# lqfp_adapters.net
KiCad netlist of a schematic drawn in EAGLE
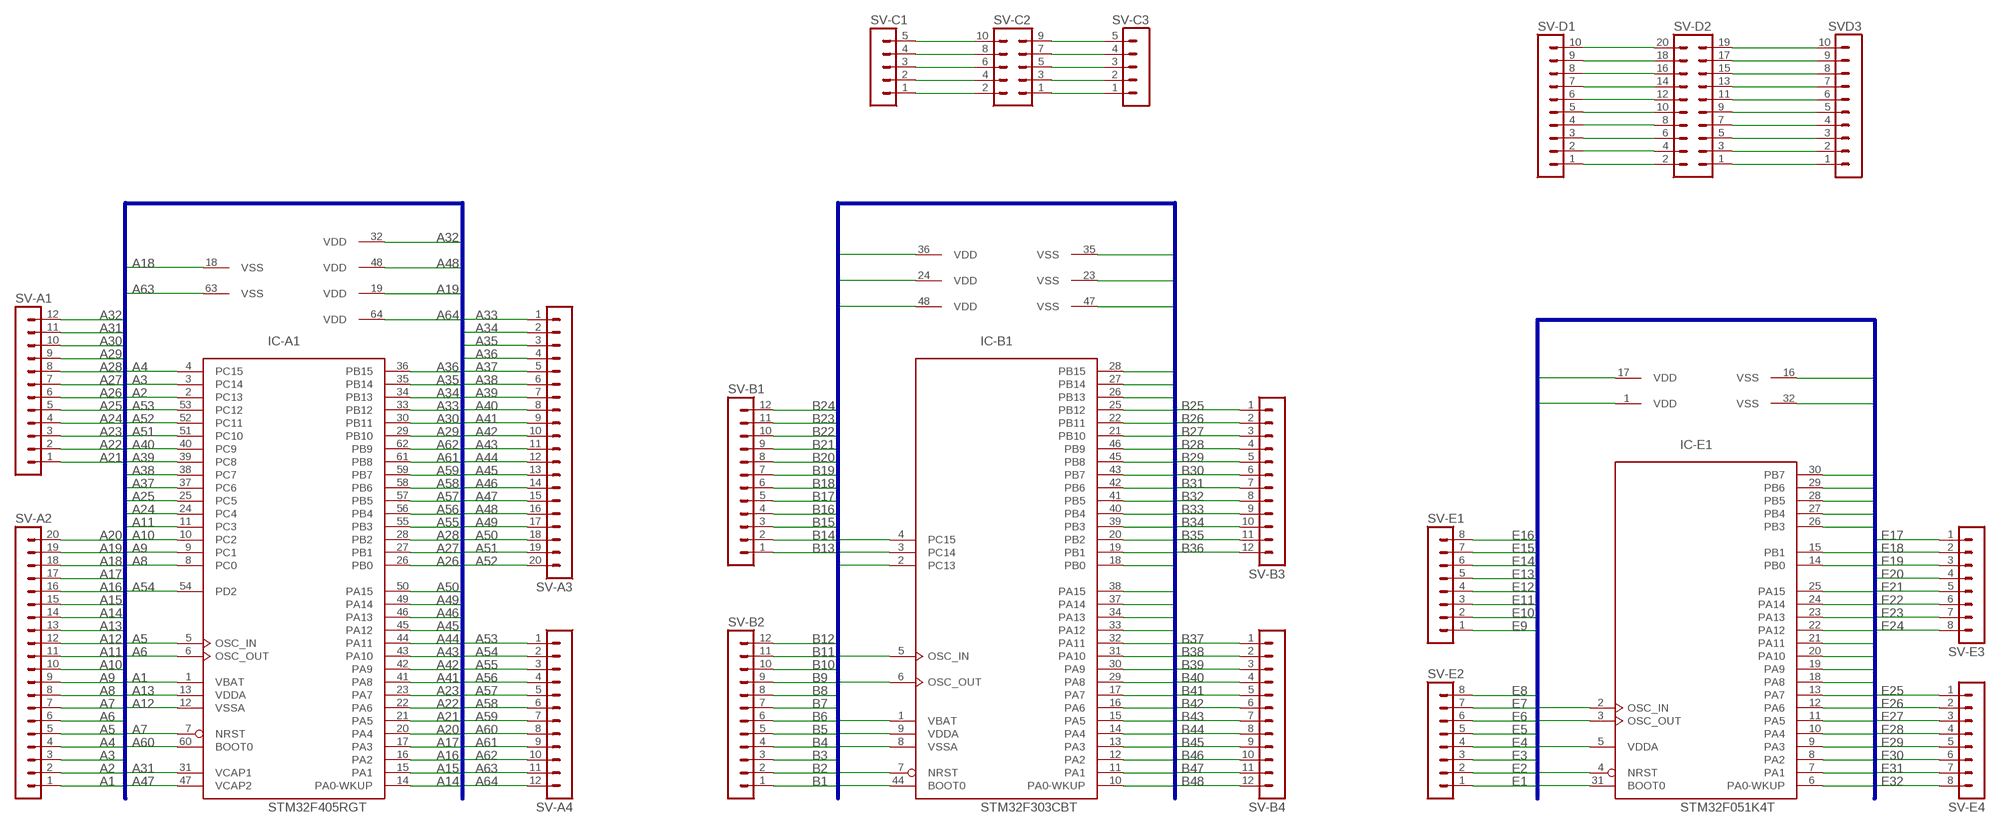
[diagram p0: schematic, sheet 1]

(export (version "E")
  (design (tool "Eeschema 10.0.6"))
  (components
    (comp (ref "IC-A1")
      (value "STM32F405RGT")
      (footprint "eagle-import:LQFP64")
      (libsource (lib "eagle-import") (part "STM32F405RTG"))
    )
    (comp (ref "IC-B1")
      (value "STM32F303CBT")
      (footprint "eagle-import:LQFP48")
      (libsource (lib "eagle-import") (part "STM32F303CTB"))
    )
    (comp (ref "IC-E1")
      (value "STM32F051K4T")
      (footprint "eagle-import:LQFP32")
      (libsource (lib "eagle-import") (part "STM32F051KT4"))
    )
    (comp (ref "SV-A1")
      (value "MA12-1NO-PL")
      (footprint "eagle-import:MA12-1-NO-PL")
      (libsource (lib "eagle-import") (part "MA12-1NO-PL"))
    )
    (comp (ref "SV-A2")
      (value "MA20-1NO-PL")
      (footprint "eagle-import:MA20-1-NO-PL")
      (libsource (lib "eagle-import") (part "MA20-1NO-PL"))
    )
    (comp (ref "SV-A3")
      (value "MA20-1NO-PL")
      (footprint "eagle-import:MA20-1-NO-PL")
      (libsource (lib "eagle-import") (part "MA20-1NO-PL"))
    )
    (comp (ref "SV-A4")
      (value "MA12-1NO-PL")
      (footprint "eagle-import:MA12-1-NO-PL")
      (libsource (lib "eagle-import") (part "MA12-1NO-PL"))
    )
    (comp (ref "SV-B1")
      (value "MA12-1NO-PL")
      (footprint "eagle-import:MA12-1-NO-PL")
      (libsource (lib "eagle-import") (part "MA12-1NO-PL"))
    )
    (comp (ref "SV-B2")
      (value "MA12-1NO-PL")
      (footprint "eagle-import:MA12-1-NO-PL")
      (libsource (lib "eagle-import") (part "MA12-1NO-PL"))
    )
    (comp (ref "SV-B3")
      (value "MA12-1NO-PL")
      (footprint "eagle-import:MA12-1-NO-PL")
      (libsource (lib "eagle-import") (part "MA12-1NO-PL"))
    )
    (comp (ref "SV-B4")
      (value "MA12-1NO-PL")
      (footprint "eagle-import:MA12-1-NO-PL")
      (libsource (lib "eagle-import") (part "MA12-1NO-PL"))
    )
    (comp (ref "SV-C1")
      (value "MA05-1NO-PL")
      (footprint "eagle-import:MA05-1-NO-PL")
      (libsource (lib "eagle-import") (part "MA05-1NO-PL"))
    )
    (comp (ref "SV-C2")
      (value "MA05-2")
      (footprint "eagle-import:MA05-2")
      (libsource (lib "eagle-import") (part "MA05-2"))
    )
    (comp (ref "SV-C3")
      (value "MA05-1NO-PL")
      (footprint "eagle-import:MA05-1-NO-PL")
      (libsource (lib "eagle-import") (part "MA05-1NO-PL"))
    )
    (comp (ref "SV-D1")
      (value "MA10-1NO-PL")
      (footprint "eagle-import:MA10-1-NO-PL")
      (libsource (lib "eagle-import") (part "MA10-1NO-PL"))
    )
    (comp (ref "SV-D2")
      (value "MA10-2")
      (footprint "eagle-import:MA10-2")
      (libsource (lib "eagle-import") (part "MA10-2"))
    )
    (comp (ref "SV-E1")
      (value "MA08-1NO-PL")
      (footprint "eagle-import:MA08-1-NO-PL")
      (libsource (lib "eagle-import") (part "MA08-1NO-PL"))
    )
    (comp (ref "SV-E2")
      (value "MA08-1NO-PL")
      (footprint "eagle-import:MA08-1-NO-PL")
      (libsource (lib "eagle-import") (part "MA08-1NO-PL"))
    )
    (comp (ref "SV-E3")
      (value "MA08-1NO-PL")
      (footprint "eagle-import:MA08-1-NO-PL")
      (libsource (lib "eagle-import") (part "MA08-1NO-PL"))
    )
    (comp (ref "SV-E4")
      (value "MA08-1NO-PL")
      (footprint "eagle-import:MA08-1-NO-PL")
      (libsource (lib "eagle-import") (part "MA08-1NO-PL"))
    )
    (comp (ref "SVD3")
      (value "MA10-1NO-PL")
      (footprint "eagle-import:MA10-1-NO-PL")
      (libsource (lib "eagle-import") (part "MA10-1NO-PL"))
    )
  )
  (nets
    (net (code "1") (name "/A1") (class "Default")
      (node (ref "IC-A1") (pin "1") (pinfunction "VBAT_1") (pintype "power_in"))
      (node (ref "SV-A2") (pin "1") (pinfunction "1_1") (pintype "passive"))
    )
    (net (code "2") (name "/A2") (class "Default")
      (node (ref "IC-A1") (pin "2") (pinfunction "PC13_2") (pintype "bidirectional"))
      (node (ref "SV-A2") (pin "2") (pinfunction "2_2") (pintype "passive"))
    )
    (net (code "3") (name "/A3") (class "Default")
      (node (ref "IC-A1") (pin "3") (pinfunction "PC14_3") (pintype "bidirectional"))
      (node (ref "SV-A2") (pin "3") (pinfunction "3_3") (pintype "passive"))
    )
    (net (code "4") (name "/A4") (class "Default")
      (node (ref "IC-A1") (pin "4") (pinfunction "PC15_4") (pintype "bidirectional"))
      (node (ref "SV-A2") (pin "4") (pinfunction "4_4") (pintype "passive"))
    )
    (net (code "5") (name "/A5") (class "Default")
      (node (ref "IC-A1") (pin "5") (pinfunction "OSC_IN_5") (pintype "bidirectional"))
      (node (ref "SV-A2") (pin "5") (pinfunction "5_5") (pintype "passive"))
    )
    (net (code "6") (name "/A6") (class "Default")
      (node (ref "IC-A1") (pin "6") (pinfunction "OSC_OUT_6") (pintype "bidirectional"))
      (node (ref "SV-A2") (pin "6") (pinfunction "6_6") (pintype "passive"))
    )
    (net (code "7") (name "/A7") (class "Default")
      (node (ref "IC-A1") (pin "7") (pinfunction "NRST_7") (pintype "bidirectional"))
      (node (ref "SV-A2") (pin "7") (pinfunction "7_7") (pintype "passive"))
    )
    (net (code "8") (name "/A8") (class "Default")
      (node (ref "IC-A1") (pin "8") (pinfunction "PC0_8") (pintype "bidirectional"))
      (node (ref "SV-A2") (pin "8") (pinfunction "8_8") (pintype "passive"))
    )
    (net (code "9") (name "/A9") (class "Default")
      (node (ref "IC-A1") (pin "9") (pinfunction "PC1_9") (pintype "bidirectional"))
      (node (ref "SV-A2") (pin "9") (pinfunction "9_9") (pintype "passive"))
    )
    (net (code "10") (name "/A10") (class "Default")
      (node (ref "IC-A1") (pin "10") (pinfunction "PC2_10") (pintype "bidirectional"))
      (node (ref "SV-A2") (pin "10") (pinfunction "10_10") (pintype "passive"))
    )
    (net (code "11") (name "/A11") (class "Default")
      (node (ref "IC-A1") (pin "11") (pinfunction "PC3_11") (pintype "bidirectional"))
      (node (ref "SV-A2") (pin "11") (pinfunction "11_11") (pintype "passive"))
    )
    (net (code "12") (name "/A12") (class "Default")
      (node (ref "IC-A1") (pin "12") (pinfunction "VSSA_12") (pintype "power_in"))
      (node (ref "SV-A2") (pin "12") (pinfunction "12_12") (pintype "passive"))
    )
    (net (code "13") (name "/A13") (class "Default")
      (node (ref "IC-A1") (pin "13") (pinfunction "VDDA_13") (pintype "power_in"))
      (node (ref "SV-A2") (pin "13") (pinfunction "13_13") (pintype "passive"))
    )
    (net (code "14") (name "/A14") (class "Default")
      (node (ref "IC-A1") (pin "14") (pinfunction "PA0-WKUP_14") (pintype "bidirectional"))
      (node (ref "SV-A2") (pin "14") (pinfunction "14_14") (pintype "passive"))
    )
    (net (code "15") (name "/A15") (class "Default")
      (node (ref "IC-A1") (pin "15") (pinfunction "PA1_15") (pintype "bidirectional"))
      (node (ref "SV-A2") (pin "15") (pinfunction "15_15") (pintype "passive"))
    )
    (net (code "16") (name "/A16") (class "Default")
      (node (ref "IC-A1") (pin "16") (pinfunction "PA2_16") (pintype "bidirectional"))
      (node (ref "SV-A2") (pin "16") (pinfunction "16_16") (pintype "passive"))
    )
    (net (code "17") (name "/A17") (class "Default")
      (node (ref "IC-A1") (pin "17") (pinfunction "PA3_17") (pintype "bidirectional"))
      (node (ref "SV-A2") (pin "17") (pinfunction "17_17") (pintype "passive"))
    )
    (net (code "18") (name "/A18") (class "Default")
      (node (ref "IC-A1") (pin "18") (pinfunction "VSS_18") (pintype "power_in"))
      (node (ref "SV-A2") (pin "18") (pinfunction "18_18") (pintype "passive"))
    )
    (net (code "19") (name "/A19") (class "Default")
      (node (ref "IC-A1") (pin "19") (pinfunction "VDD_19") (pintype "power_in"))
      (node (ref "SV-A2") (pin "19") (pinfunction "19_19") (pintype "passive"))
    )
    (net (code "20") (name "/A20") (class "Default")
      (node (ref "IC-A1") (pin "20") (pinfunction "PA4_20") (pintype "bidirectional"))
      (node (ref "SV-A2") (pin "20") (pinfunction "20_20") (pintype "passive"))
    )
    (net (code "21") (name "/A21") (class "Default")
      (node (ref "IC-A1") (pin "21") (pinfunction "PA5_21") (pintype "bidirectional"))
      (node (ref "SV-A1") (pin "1") (pinfunction "1_1") (pintype "passive"))
    )
    (net (code "22") (name "/A22") (class "Default")
      (node (ref "IC-A1") (pin "22") (pinfunction "PA6_22") (pintype "bidirectional"))
      (node (ref "SV-A1") (pin "2") (pinfunction "2_2") (pintype "passive"))
    )
    (net (code "23") (name "/A23") (class "Default")
      (node (ref "IC-A1") (pin "23") (pinfunction "PA7_23") (pintype "bidirectional"))
      (node (ref "SV-A1") (pin "3") (pinfunction "3_3") (pintype "passive"))
    )
    (net (code "24") (name "/A24") (class "Default")
      (node (ref "IC-A1") (pin "24") (pinfunction "PC4_24") (pintype "bidirectional"))
      (node (ref "SV-A1") (pin "4") (pinfunction "4_4") (pintype "passive"))
    )
    (net (code "25") (name "/A25") (class "Default")
      (node (ref "IC-A1") (pin "25") (pinfunction "PC5_25") (pintype "bidirectional"))
      (node (ref "SV-A1") (pin "5") (pinfunction "5_5") (pintype "passive"))
    )
    (net (code "26") (name "/A26") (class "Default")
      (node (ref "IC-A1") (pin "26") (pinfunction "PB0_26") (pintype "bidirectional"))
      (node (ref "SV-A1") (pin "6") (pinfunction "6_6") (pintype "passive"))
    )
    (net (code "27") (name "/A27") (class "Default")
      (node (ref "IC-A1") (pin "27") (pinfunction "PB1_27") (pintype "bidirectional"))
      (node (ref "SV-A1") (pin "7") (pinfunction "7_7") (pintype "passive"))
    )
    (net (code "28") (name "/A28") (class "Default")
      (node (ref "IC-A1") (pin "28") (pinfunction "PB2_28") (pintype "bidirectional"))
      (node (ref "SV-A1") (pin "8") (pinfunction "8_8") (pintype "passive"))
    )
    (net (code "29") (name "/A29") (class "Default")
      (node (ref "IC-A1") (pin "29") (pinfunction "PB10_29") (pintype "bidirectional"))
      (node (ref "SV-A1") (pin "9") (pinfunction "9_9") (pintype "passive"))
    )
    (net (code "30") (name "/A30") (class "Default")
      (node (ref "IC-A1") (pin "30") (pinfunction "PB11_30") (pintype "bidirectional"))
      (node (ref "SV-A1") (pin "10") (pinfunction "10_10") (pintype "passive"))
    )
    (net (code "31") (name "/A31") (class "Default")
      (node (ref "IC-A1") (pin "31") (pinfunction "VCAP1_31") (pintype "power_in"))
      (node (ref "SV-A1") (pin "11") (pinfunction "11_11") (pintype "passive"))
    )
    (net (code "32") (name "/A32") (class "Default")
      (node (ref "IC-A1") (pin "32") (pinfunction "VDD_32") (pintype "power_in"))
      (node (ref "SV-A1") (pin "12") (pinfunction "12_12") (pintype "passive"))
    )
    (net (code "33") (name "/A33") (class "Default")
      (node (ref "IC-A1") (pin "33") (pinfunction "PB12_33") (pintype "bidirectional"))
      (node (ref "SV-A3") (pin "1") (pinfunction "1_1") (pintype "passive"))
    )
    (net (code "34") (name "/A34") (class "Default")
      (node (ref "IC-A1") (pin "34") (pinfunction "PB13_34") (pintype "bidirectional"))
      (node (ref "SV-A3") (pin "2") (pinfunction "2_2") (pintype "passive"))
    )
    (net (code "35") (name "/A35") (class "Default")
      (node (ref "IC-A1") (pin "35") (pinfunction "PB14_35") (pintype "bidirectional"))
      (node (ref "SV-A3") (pin "3") (pinfunction "3_3") (pintype "passive"))
    )
    (net (code "36") (name "/A36") (class "Default")
      (node (ref "IC-A1") (pin "36") (pinfunction "PB15_36") (pintype "bidirectional"))
      (node (ref "SV-A3") (pin "4") (pinfunction "4_4") (pintype "passive"))
    )
    (net (code "37") (name "/A37") (class "Default")
      (node (ref "IC-A1") (pin "37") (pinfunction "PC6_37") (pintype "bidirectional"))
      (node (ref "SV-A3") (pin "5") (pinfunction "5_5") (pintype "passive"))
    )
    (net (code "38") (name "/A38") (class "Default")
      (node (ref "IC-A1") (pin "38") (pinfunction "PC7_38") (pintype "bidirectional"))
      (node (ref "SV-A3") (pin "6") (pinfunction "6_6") (pintype "passive"))
    )
    (net (code "39") (name "/A39") (class "Default")
      (node (ref "IC-A1") (pin "39") (pinfunction "PC8_39") (pintype "bidirectional"))
      (node (ref "SV-A3") (pin "7") (pinfunction "7_7") (pintype "passive"))
    )
    (net (code "40") (name "/A40") (class "Default")
      (node (ref "IC-A1") (pin "40") (pinfunction "PC9_40") (pintype "bidirectional"))
      (node (ref "SV-A3") (pin "8") (pinfunction "8_8") (pintype "passive"))
    )
    (net (code "41") (name "/A41") (class "Default")
      (node (ref "IC-A1") (pin "41") (pinfunction "PA8_41") (pintype "bidirectional"))
      (node (ref "SV-A3") (pin "9") (pinfunction "9_9") (pintype "passive"))
    )
    (net (code "42") (name "/A42") (class "Default")
      (node (ref "IC-A1") (pin "42") (pinfunction "PA9_42") (pintype "bidirectional"))
      (node (ref "SV-A3") (pin "10") (pinfunction "10_10") (pintype "passive"))
    )
    (net (code "43") (name "/A43") (class "Default")
      (node (ref "IC-A1") (pin "43") (pinfunction "PA10_43") (pintype "bidirectional"))
      (node (ref "SV-A3") (pin "11") (pinfunction "11_11") (pintype "passive"))
    )
    (net (code "44") (name "/A44") (class "Default")
      (node (ref "IC-A1") (pin "44") (pinfunction "PA11_44") (pintype "bidirectional"))
      (node (ref "SV-A3") (pin "12") (pinfunction "12_12") (pintype "passive"))
    )
    (net (code "45") (name "/A45") (class "Default")
      (node (ref "IC-A1") (pin "45") (pinfunction "PA12_45") (pintype "bidirectional"))
      (node (ref "SV-A3") (pin "13") (pinfunction "13_13") (pintype "passive"))
    )
    (net (code "46") (name "/A46") (class "Default")
      (node (ref "IC-A1") (pin "46") (pinfunction "PA13_46") (pintype "bidirectional"))
      (node (ref "SV-A3") (pin "14") (pinfunction "14_14") (pintype "passive"))
    )
    (net (code "47") (name "/A47") (class "Default")
      (node (ref "IC-A1") (pin "47") (pinfunction "VCAP2_47") (pintype "power_in"))
      (node (ref "SV-A3") (pin "15") (pinfunction "15_15") (pintype "passive"))
    )
    (net (code "48") (name "/A48") (class "Default")
      (node (ref "IC-A1") (pin "48") (pinfunction "VDD_48") (pintype "power_in"))
      (node (ref "SV-A3") (pin "16") (pinfunction "16_16") (pintype "passive"))
    )
    (net (code "49") (name "/A49") (class "Default")
      (node (ref "IC-A1") (pin "49") (pinfunction "PA14_49") (pintype "bidirectional"))
      (node (ref "SV-A3") (pin "17") (pinfunction "17_17") (pintype "passive"))
    )
    (net (code "50") (name "/A50") (class "Default")
      (node (ref "IC-A1") (pin "50") (pinfunction "PA15_50") (pintype "bidirectional"))
      (node (ref "SV-A3") (pin "18") (pinfunction "18_18") (pintype "passive"))
    )
    (net (code "51") (name "/A51") (class "Default")
      (node (ref "IC-A1") (pin "51") (pinfunction "PC10_51") (pintype "bidirectional"))
      (node (ref "SV-A3") (pin "19") (pinfunction "19_19") (pintype "passive"))
    )
    (net (code "52") (name "/A52") (class "Default")
      (node (ref "IC-A1") (pin "52") (pinfunction "PC11_52") (pintype "bidirectional"))
      (node (ref "SV-A3") (pin "20") (pinfunction "20_20") (pintype "passive"))
    )
    (net (code "53") (name "/A53") (class "Default")
      (node (ref "IC-A1") (pin "53") (pinfunction "PC12_53") (pintype "bidirectional"))
      (node (ref "SV-A4") (pin "1") (pinfunction "1_1") (pintype "passive"))
    )
    (net (code "54") (name "/A54") (class "Default")
      (node (ref "IC-A1") (pin "54") (pinfunction "PD2_54") (pintype "bidirectional"))
      (node (ref "SV-A4") (pin "2") (pinfunction "2_2") (pintype "passive"))
    )
    (net (code "55") (name "/A55") (class "Default")
      (node (ref "IC-A1") (pin "55") (pinfunction "PB3_55") (pintype "bidirectional"))
      (node (ref "SV-A4") (pin "3") (pinfunction "3_3") (pintype "passive"))
    )
    (net (code "56") (name "/A56") (class "Default")
      (node (ref "IC-A1") (pin "56") (pinfunction "PB4_56") (pintype "bidirectional"))
      (node (ref "SV-A4") (pin "4") (pinfunction "4_4") (pintype "passive"))
    )
    (net (code "57") (name "/A57") (class "Default")
      (node (ref "IC-A1") (pin "57") (pinfunction "PB5_57") (pintype "bidirectional"))
      (node (ref "SV-A4") (pin "5") (pinfunction "5_5") (pintype "passive"))
    )
    (net (code "58") (name "/A58") (class "Default")
      (node (ref "IC-A1") (pin "58") (pinfunction "PB6_58") (pintype "bidirectional"))
      (node (ref "SV-A4") (pin "6") (pinfunction "6_6") (pintype "passive"))
    )
    (net (code "59") (name "/A59") (class "Default")
      (node (ref "IC-A1") (pin "59") (pinfunction "PB7_59") (pintype "bidirectional"))
      (node (ref "SV-A4") (pin "7") (pinfunction "7_7") (pintype "passive"))
    )
    (net (code "60") (name "/A60") (class "Default")
      (node (ref "IC-A1") (pin "60") (pinfunction "BOOT0_60") (pintype "input"))
      (node (ref "SV-A4") (pin "8") (pinfunction "8_8") (pintype "passive"))
    )
    (net (code "61") (name "/A61") (class "Default")
      (node (ref "IC-A1") (pin "61") (pinfunction "PB8_61") (pintype "bidirectional"))
      (node (ref "SV-A4") (pin "9") (pinfunction "9_9") (pintype "passive"))
    )
    (net (code "62") (name "/A62") (class "Default")
      (node (ref "IC-A1") (pin "62") (pinfunction "PB9_62") (pintype "bidirectional"))
      (node (ref "SV-A4") (pin "10") (pinfunction "10_10") (pintype "passive"))
    )
    (net (code "63") (name "/A63") (class "Default")
      (node (ref "IC-A1") (pin "63") (pinfunction "VSS_63") (pintype "power_in"))
      (node (ref "SV-A4") (pin "11") (pinfunction "11_11") (pintype "passive"))
    )
    (net (code "64") (name "/A64") (class "Default")
      (node (ref "IC-A1") (pin "64") (pinfunction "VDD_64") (pintype "power_in"))
      (node (ref "SV-A4") (pin "12") (pinfunction "12_12") (pintype "passive"))
    )
    (net (code "65") (name "/B1") (class "Default")
      (node (ref "IC-B1") (pin "1") (pinfunction "VBAT_1") (pintype "power_in"))
      (node (ref "SV-B2") (pin "1") (pinfunction "1_1") (pintype "passive"))
    )
    (net (code "66") (name "/B2") (class "Default")
      (node (ref "IC-B1") (pin "2") (pinfunction "PC13_2") (pintype "bidirectional"))
      (node (ref "SV-B2") (pin "2") (pinfunction "2_2") (pintype "passive"))
    )
    (net (code "67") (name "/B3") (class "Default")
      (node (ref "IC-B1") (pin "3") (pinfunction "PC14_3") (pintype "bidirectional"))
      (node (ref "SV-B2") (pin "3") (pinfunction "3_3") (pintype "passive"))
    )
    (net (code "68") (name "/B4") (class "Default")
      (node (ref "IC-B1") (pin "4") (pinfunction "PC15_4") (pintype "bidirectional"))
      (node (ref "SV-B2") (pin "4") (pinfunction "4_4") (pintype "passive"))
    )
    (net (code "69") (name "/B5") (class "Default")
      (node (ref "IC-B1") (pin "5") (pinfunction "OSC_IN_5") (pintype "bidirectional"))
      (node (ref "SV-B2") (pin "5") (pinfunction "5_5") (pintype "passive"))
    )
    (net (code "70") (name "/B6") (class "Default")
      (node (ref "IC-B1") (pin "6") (pinfunction "OSC_OUT_6") (pintype "bidirectional"))
      (node (ref "SV-B2") (pin "6") (pinfunction "6_6") (pintype "passive"))
    )
    (net (code "71") (name "/B7") (class "Default")
      (node (ref "IC-B1") (pin "7") (pinfunction "NRST_7") (pintype "bidirectional"))
      (node (ref "SV-B2") (pin "7") (pinfunction "7_7") (pintype "passive"))
    )
    (net (code "72") (name "/B8") (class "Default")
      (node (ref "IC-B1") (pin "8") (pinfunction "VSSA_8") (pintype "power_in"))
      (node (ref "SV-B2") (pin "8") (pinfunction "8_8") (pintype "passive"))
    )
    (net (code "73") (name "/B9") (class "Default")
      (node (ref "IC-B1") (pin "9") (pinfunction "VDDA_9") (pintype "power_in"))
      (node (ref "SV-B2") (pin "9") (pinfunction "9_9") (pintype "passive"))
    )
    (net (code "74") (name "/B10") (class "Default")
      (node (ref "IC-B1") (pin "10") (pinfunction "PA0-WKUP_10") (pintype "bidirectional"))
      (node (ref "SV-B2") (pin "10") (pinfunction "10_10") (pintype "passive"))
    )
    (net (code "75") (name "/B11") (class "Default")
      (node (ref "IC-B1") (pin "11") (pinfunction "PA1_11") (pintype "bidirectional"))
      (node (ref "SV-B2") (pin "11") (pinfunction "11_11") (pintype "passive"))
    )
    (net (code "76") (name "/B12") (class "Default")
      (node (ref "IC-B1") (pin "12") (pinfunction "PA2_12") (pintype "bidirectional"))
      (node (ref "SV-B2") (pin "12") (pinfunction "12_12") (pintype "passive"))
    )
    (net (code "77") (name "/B13") (class "Default")
      (node (ref "IC-B1") (pin "13") (pinfunction "PA3_13") (pintype "bidirectional"))
      (node (ref "SV-B1") (pin "1") (pinfunction "1_1") (pintype "passive"))
    )
    (net (code "78") (name "/B14") (class "Default")
      (node (ref "IC-B1") (pin "14") (pinfunction "PA4_14") (pintype "bidirectional"))
      (node (ref "SV-B1") (pin "2") (pinfunction "2_2") (pintype "passive"))
    )
    (net (code "79") (name "/B15") (class "Default")
      (node (ref "IC-B1") (pin "15") (pinfunction "PA5_15") (pintype "bidirectional"))
      (node (ref "SV-B1") (pin "3") (pinfunction "3_3") (pintype "passive"))
    )
    (net (code "80") (name "/B16") (class "Default")
      (node (ref "IC-B1") (pin "16") (pinfunction "PA6_16") (pintype "bidirectional"))
      (node (ref "SV-B1") (pin "4") (pinfunction "4_4") (pintype "passive"))
    )
    (net (code "81") (name "/B17") (class "Default")
      (node (ref "IC-B1") (pin "17") (pinfunction "PA7_17") (pintype "bidirectional"))
      (node (ref "SV-B1") (pin "5") (pinfunction "5_5") (pintype "passive"))
    )
    (net (code "82") (name "/B18") (class "Default")
      (node (ref "IC-B1") (pin "18") (pinfunction "PB0_18") (pintype "bidirectional"))
      (node (ref "SV-B1") (pin "6") (pinfunction "6_6") (pintype "passive"))
    )
    (net (code "83") (name "/B19") (class "Default")
      (node (ref "IC-B1") (pin "19") (pinfunction "PB1_19") (pintype "bidirectional"))
      (node (ref "SV-B1") (pin "7") (pinfunction "7_7") (pintype "passive"))
    )
    (net (code "84") (name "/B20") (class "Default")
      (node (ref "IC-B1") (pin "20") (pinfunction "PB2_20") (pintype "bidirectional"))
      (node (ref "SV-B1") (pin "8") (pinfunction "8_8") (pintype "passive"))
    )
    (net (code "85") (name "/B21") (class "Default")
      (node (ref "IC-B1") (pin "21") (pinfunction "PB10_21") (pintype "bidirectional"))
      (node (ref "SV-B1") (pin "9") (pinfunction "9_9") (pintype "passive"))
    )
    (net (code "86") (name "/B22") (class "Default")
      (node (ref "IC-B1") (pin "22") (pinfunction "PB11_22") (pintype "bidirectional"))
      (node (ref "SV-B1") (pin "10") (pinfunction "10_10") (pintype "passive"))
    )
    (net (code "87") (name "/B23") (class "Default")
      (node (ref "IC-B1") (pin "23") (pinfunction "VSS_23") (pintype "power_in"))
      (node (ref "SV-B1") (pin "11") (pinfunction "11_11") (pintype "passive"))
    )
    (net (code "88") (name "/B24") (class "Default")
      (node (ref "IC-B1") (pin "24") (pinfunction "VDD_24") (pintype "power_in"))
      (node (ref "SV-B1") (pin "12") (pinfunction "12_12") (pintype "passive"))
    )
    (net (code "89") (name "/B25") (class "Default")
      (node (ref "IC-B1") (pin "25") (pinfunction "PB12_25") (pintype "bidirectional"))
      (node (ref "SV-B3") (pin "1") (pinfunction "1_1") (pintype "passive"))
    )
    (net (code "90") (name "/B26") (class "Default")
      (node (ref "IC-B1") (pin "26") (pinfunction "PB13_26") (pintype "bidirectional"))
      (node (ref "SV-B3") (pin "2") (pinfunction "2_2") (pintype "passive"))
    )
    (net (code "91") (name "/B27") (class "Default")
      (node (ref "IC-B1") (pin "27") (pinfunction "PB14_27") (pintype "bidirectional"))
      (node (ref "SV-B3") (pin "3") (pinfunction "3_3") (pintype "passive"))
    )
    (net (code "92") (name "/B28") (class "Default")
      (node (ref "IC-B1") (pin "28") (pinfunction "PB15_28") (pintype "bidirectional"))
      (node (ref "SV-B3") (pin "4") (pinfunction "4_4") (pintype "passive"))
    )
    (net (code "93") (name "/B29") (class "Default")
      (node (ref "IC-B1") (pin "29") (pinfunction "PA8_29") (pintype "bidirectional"))
      (node (ref "SV-B3") (pin "5") (pinfunction "5_5") (pintype "passive"))
    )
    (net (code "94") (name "/B30") (class "Default")
      (node (ref "IC-B1") (pin "30") (pinfunction "PA9_30") (pintype "bidirectional"))
      (node (ref "SV-B3") (pin "6") (pinfunction "6_6") (pintype "passive"))
    )
    (net (code "95") (name "/B31") (class "Default")
      (node (ref "IC-B1") (pin "31") (pinfunction "PA10_31") (pintype "bidirectional"))
      (node (ref "SV-B3") (pin "7") (pinfunction "7_7") (pintype "passive"))
    )
    (net (code "96") (name "/B32") (class "Default")
      (node (ref "IC-B1") (pin "32") (pinfunction "PA11_32") (pintype "bidirectional"))
      (node (ref "SV-B3") (pin "8") (pinfunction "8_8") (pintype "passive"))
    )
    (net (code "97") (name "/B33") (class "Default")
      (node (ref "IC-B1") (pin "33") (pinfunction "PA12_33") (pintype "bidirectional"))
      (node (ref "SV-B3") (pin "9") (pinfunction "9_9") (pintype "passive"))
    )
    (net (code "98") (name "/B34") (class "Default")
      (node (ref "IC-B1") (pin "34") (pinfunction "PA13_34") (pintype "bidirectional"))
      (node (ref "SV-B3") (pin "10") (pinfunction "10_10") (pintype "passive"))
    )
    (net (code "99") (name "/B35") (class "Default")
      (node (ref "IC-B1") (pin "35") (pinfunction "VSS_35") (pintype "power_in"))
      (node (ref "SV-B3") (pin "11") (pinfunction "11_11") (pintype "passive"))
    )
    (net (code "100") (name "/B36") (class "Default")
      (node (ref "IC-B1") (pin "36") (pinfunction "VDD_36") (pintype "power_in"))
      (node (ref "SV-B3") (pin "12") (pinfunction "12_12") (pintype "passive"))
    )
    (net (code "101") (name "/B37") (class "Default")
      (node (ref "IC-B1") (pin "37") (pinfunction "PA14_37") (pintype "bidirectional"))
      (node (ref "SV-B4") (pin "1") (pinfunction "1_1") (pintype "passive"))
    )
    (net (code "102") (name "/B38") (class "Default")
      (node (ref "IC-B1") (pin "38") (pinfunction "PA15_38") (pintype "bidirectional"))
      (node (ref "SV-B4") (pin "2") (pinfunction "2_2") (pintype "passive"))
    )
    (net (code "103") (name "/B39") (class "Default")
      (node (ref "IC-B1") (pin "39") (pinfunction "PB3_39") (pintype "bidirectional"))
      (node (ref "SV-B4") (pin "3") (pinfunction "3_3") (pintype "passive"))
    )
    (net (code "104") (name "/B40") (class "Default")
      (node (ref "IC-B1") (pin "40") (pinfunction "PB4_40") (pintype "bidirectional"))
      (node (ref "SV-B4") (pin "4") (pinfunction "4_4") (pintype "passive"))
    )
    (net (code "105") (name "/B41") (class "Default")
      (node (ref "IC-B1") (pin "41") (pinfunction "PB5_41") (pintype "bidirectional"))
      (node (ref "SV-B4") (pin "5") (pinfunction "5_5") (pintype "passive"))
    )
    (net (code "106") (name "/B42") (class "Default")
      (node (ref "IC-B1") (pin "42") (pinfunction "PB6_42") (pintype "bidirectional"))
      (node (ref "SV-B4") (pin "6") (pinfunction "6_6") (pintype "passive"))
    )
    (net (code "107") (name "/B43") (class "Default")
      (node (ref "IC-B1") (pin "43") (pinfunction "PB7_43") (pintype "bidirectional"))
      (node (ref "SV-B4") (pin "7") (pinfunction "7_7") (pintype "passive"))
    )
    (net (code "108") (name "/B44") (class "Default")
      (node (ref "IC-B1") (pin "44") (pinfunction "BOOT0_44") (pintype "input"))
      (node (ref "SV-B4") (pin "8") (pinfunction "8_8") (pintype "passive"))
    )
    (net (code "109") (name "/B45") (class "Default")
      (node (ref "IC-B1") (pin "45") (pinfunction "PB8_45") (pintype "bidirectional"))
      (node (ref "SV-B4") (pin "9") (pinfunction "9_9") (pintype "passive"))
    )
    (net (code "110") (name "/B46") (class "Default")
      (node (ref "IC-B1") (pin "46") (pinfunction "PB9_46") (pintype "bidirectional"))
      (node (ref "SV-B4") (pin "10") (pinfunction "10_10") (pintype "passive"))
    )
    (net (code "111") (name "/B47") (class "Default")
      (node (ref "IC-B1") (pin "47") (pinfunction "VSS_47") (pintype "power_in"))
      (node (ref "SV-B4") (pin "11") (pinfunction "11_11") (pintype "passive"))
    )
    (net (code "112") (name "/B48") (class "Default")
      (node (ref "IC-B1") (pin "48") (pinfunction "VDD_48") (pintype "power_in"))
      (node (ref "SV-B4") (pin "12") (pinfunction "12_12") (pintype "passive"))
    )
    (net (code "113") (name "/E1") (class "Default")
      (node (ref "IC-E1") (pin "1") (pinfunction "VDD_1") (pintype "power_in"))
      (node (ref "SV-E2") (pin "1") (pinfunction "1_1") (pintype "passive"))
    )
    (net (code "114") (name "/E2") (class "Default")
      (node (ref "IC-E1") (pin "2") (pinfunction "OSC_IN_2") (pintype "bidirectional"))
      (node (ref "SV-E2") (pin "2") (pinfunction "2_2") (pintype "passive"))
    )
    (net (code "115") (name "/E3") (class "Default")
      (node (ref "IC-E1") (pin "3") (pinfunction "OSC_OUT_3") (pintype "bidirectional"))
      (node (ref "SV-E2") (pin "3") (pinfunction "3_3") (pintype "passive"))
    )
    (net (code "116") (name "/E4") (class "Default")
      (node (ref "IC-E1") (pin "4") (pinfunction "NRST_4") (pintype "bidirectional"))
      (node (ref "SV-E2") (pin "4") (pinfunction "4_4") (pintype "passive"))
    )
    (net (code "117") (name "/E5") (class "Default")
      (node (ref "IC-E1") (pin "5") (pinfunction "VDDA_5") (pintype "power_in"))
      (node (ref "SV-E2") (pin "5") (pinfunction "5_5") (pintype "passive"))
    )
    (net (code "118") (name "/E6") (class "Default")
      (node (ref "IC-E1") (pin "6") (pinfunction "PA0-WKUP_6") (pintype "bidirectional"))
      (node (ref "SV-E2") (pin "6") (pinfunction "6_6") (pintype "passive"))
    )
    (net (code "119") (name "/E7") (class "Default")
      (node (ref "IC-E1") (pin "7") (pinfunction "PA1_7") (pintype "bidirectional"))
      (node (ref "SV-E2") (pin "7") (pinfunction "7_7") (pintype "passive"))
    )
    (net (code "120") (name "/E8") (class "Default")
      (node (ref "IC-E1") (pin "8") (pinfunction "PA2_8") (pintype "bidirectional"))
      (node (ref "SV-E2") (pin "8") (pinfunction "8_8") (pintype "passive"))
    )
    (net (code "121") (name "/E9") (class "Default")
      (node (ref "IC-E1") (pin "9") (pinfunction "PA3_9") (pintype "bidirectional"))
      (node (ref "SV-E1") (pin "1") (pinfunction "1_1") (pintype "passive"))
    )
    (net (code "122") (name "/E10") (class "Default")
      (node (ref "IC-E1") (pin "10") (pinfunction "PA4_10") (pintype "bidirectional"))
      (node (ref "SV-E1") (pin "2") (pinfunction "2_2") (pintype "passive"))
    )
    (net (code "123") (name "/E11") (class "Default")
      (node (ref "IC-E1") (pin "11") (pinfunction "PA5_11") (pintype "bidirectional"))
      (node (ref "SV-E1") (pin "3") (pinfunction "3_3") (pintype "passive"))
    )
    (net (code "124") (name "/E12") (class "Default")
      (node (ref "IC-E1") (pin "12") (pinfunction "PA6_12") (pintype "bidirectional"))
      (node (ref "SV-E1") (pin "4") (pinfunction "4_4") (pintype "passive"))
    )
    (net (code "125") (name "/E13") (class "Default")
      (node (ref "IC-E1") (pin "13") (pinfunction "PA7_13") (pintype "bidirectional"))
      (node (ref "SV-E1") (pin "5") (pinfunction "5_5") (pintype "passive"))
    )
    (net (code "126") (name "/E14") (class "Default")
      (node (ref "IC-E1") (pin "14") (pinfunction "PB0_14") (pintype "bidirectional"))
      (node (ref "SV-E1") (pin "6") (pinfunction "6_6") (pintype "passive"))
    )
    (net (code "127") (name "/E15") (class "Default")
      (node (ref "IC-E1") (pin "15") (pinfunction "PB1_15") (pintype "bidirectional"))
      (node (ref "SV-E1") (pin "7") (pinfunction "7_7") (pintype "passive"))
    )
    (net (code "128") (name "/E16") (class "Default")
      (node (ref "IC-E1") (pin "16") (pinfunction "VSS_16") (pintype "power_in"))
      (node (ref "SV-E1") (pin "8") (pinfunction "8_8") (pintype "passive"))
    )
    (net (code "129") (name "/E17") (class "Default")
      (node (ref "IC-E1") (pin "17") (pinfunction "VDD_17") (pintype "power_in"))
      (node (ref "SV-E3") (pin "1") (pinfunction "1_1") (pintype "passive"))
    )
    (net (code "130") (name "/E18") (class "Default")
      (node (ref "IC-E1") (pin "18") (pinfunction "PA8_18") (pintype "bidirectional"))
      (node (ref "SV-E3") (pin "2") (pinfunction "2_2") (pintype "passive"))
    )
    (net (code "131") (name "/E19") (class "Default")
      (node (ref "IC-E1") (pin "19") (pinfunction "PA9_19") (pintype "bidirectional"))
      (node (ref "SV-E3") (pin "3") (pinfunction "3_3") (pintype "passive"))
    )
    (net (code "132") (name "/E20") (class "Default")
      (node (ref "IC-E1") (pin "20") (pinfunction "PA10_20") (pintype "bidirectional"))
      (node (ref "SV-E3") (pin "4") (pinfunction "4_4") (pintype "passive"))
    )
    (net (code "133") (name "/E21") (class "Default")
      (node (ref "IC-E1") (pin "21") (pinfunction "PA11_21") (pintype "bidirectional"))
      (node (ref "SV-E3") (pin "5") (pinfunction "5_5") (pintype "passive"))
    )
    (net (code "134") (name "/E22") (class "Default")
      (node (ref "IC-E1") (pin "22") (pinfunction "PA12_22") (pintype "bidirectional"))
      (node (ref "SV-E3") (pin "6") (pinfunction "6_6") (pintype "passive"))
    )
    (net (code "135") (name "/E23") (class "Default")
      (node (ref "IC-E1") (pin "23") (pinfunction "PA13_23") (pintype "bidirectional"))
      (node (ref "SV-E3") (pin "7") (pinfunction "7_7") (pintype "passive"))
    )
    (net (code "136") (name "/E24") (class "Default")
      (node (ref "IC-E1") (pin "24") (pinfunction "PA14_24") (pintype "bidirectional"))
      (node (ref "SV-E3") (pin "8") (pinfunction "8_8") (pintype "passive"))
    )
    (net (code "137") (name "/E25") (class "Default")
      (node (ref "IC-E1") (pin "25") (pinfunction "PA15_25") (pintype "bidirectional"))
      (node (ref "SV-E4") (pin "1") (pinfunction "1_1") (pintype "passive"))
    )
    (net (code "138") (name "/E26") (class "Default")
      (node (ref "IC-E1") (pin "26") (pinfunction "PB3_26") (pintype "bidirectional"))
      (node (ref "SV-E4") (pin "2") (pinfunction "2_2") (pintype "passive"))
    )
    (net (code "139") (name "/E27") (class "Default")
      (node (ref "IC-E1") (pin "27") (pinfunction "PB4_27") (pintype "bidirectional"))
      (node (ref "SV-E4") (pin "3") (pinfunction "3_3") (pintype "passive"))
    )
    (net (code "140") (name "/E28") (class "Default")
      (node (ref "IC-E1") (pin "28") (pinfunction "PB5_28") (pintype "bidirectional"))
      (node (ref "SV-E4") (pin "4") (pinfunction "4_4") (pintype "passive"))
    )
    (net (code "141") (name "/E29") (class "Default")
      (node (ref "IC-E1") (pin "29") (pinfunction "PB6_29") (pintype "bidirectional"))
      (node (ref "SV-E4") (pin "5") (pinfunction "5_5") (pintype "passive"))
    )
    (net (code "142") (name "/E30") (class "Default")
      (node (ref "IC-E1") (pin "30") (pinfunction "PB7_30") (pintype "bidirectional"))
      (node (ref "SV-E4") (pin "6") (pinfunction "6_6") (pintype "passive"))
    )
    (net (code "143") (name "/E31") (class "Default")
      (node (ref "IC-E1") (pin "31") (pinfunction "BOOT0_31") (pintype "input"))
      (node (ref "SV-E4") (pin "7") (pinfunction "7_7") (pintype "passive"))
    )
    (net (code "144") (name "/E32") (class "Default")
      (node (ref "IC-E1") (pin "32") (pinfunction "VSS_32") (pintype "power_in"))
      (node (ref "SV-E4") (pin "8") (pinfunction "8_8") (pintype "passive"))
    )
    (net (code "145") (name "Net-(SV-C1-Pad1)") (class "Default")
      (node (ref "SV-C1") (pin "1") (pinfunction "1_1") (pintype "passive"))
      (node (ref "SV-C2") (pin "2") (pinfunction "2_2") (pintype "passive"))
    )
    (net (code "146") (name "Net-(SV-C1-Pad2)") (class "Default")
      (node (ref "SV-C1") (pin "2") (pinfunction "2_2") (pintype "passive"))
      (node (ref "SV-C2") (pin "4") (pinfunction "4_4") (pintype "passive"))
    )
    (net (code "147") (name "Net-(SV-C1-Pad3)") (class "Default")
      (node (ref "SV-C1") (pin "3") (pinfunction "3_3") (pintype "passive"))
      (node (ref "SV-C2") (pin "6") (pinfunction "6_6") (pintype "passive"))
    )
    (net (code "148") (name "Net-(SV-C1-Pad4)") (class "Default")
      (node (ref "SV-C1") (pin "4") (pinfunction "4_4") (pintype "passive"))
      (node (ref "SV-C2") (pin "8") (pinfunction "8_8") (pintype "passive"))
    )
    (net (code "149") (name "Net-(SV-C1-Pad5)") (class "Default")
      (node (ref "SV-C1") (pin "5") (pinfunction "5_5") (pintype "passive"))
      (node (ref "SV-C2") (pin "10") (pinfunction "10_10") (pintype "passive"))
    )
    (net (code "150") (name "Net-(SV-C2-Pad1)") (class "Default")
      (node (ref "SV-C2") (pin "1") (pinfunction "1_1") (pintype "passive"))
      (node (ref "SV-C3") (pin "1") (pinfunction "1_1") (pintype "passive"))
    )
    (net (code "151") (name "Net-(SV-C2-Pad3)") (class "Default")
      (node (ref "SV-C2") (pin "3") (pinfunction "3_3") (pintype "passive"))
      (node (ref "SV-C3") (pin "2") (pinfunction "2_2") (pintype "passive"))
    )
    (net (code "152") (name "Net-(SV-C2-Pad5)") (class "Default")
      (node (ref "SV-C2") (pin "5") (pinfunction "5_5") (pintype "passive"))
      (node (ref "SV-C3") (pin "3") (pinfunction "3_3") (pintype "passive"))
    )
    (net (code "153") (name "Net-(SV-C2-Pad7)") (class "Default")
      (node (ref "SV-C2") (pin "7") (pinfunction "7_7") (pintype "passive"))
      (node (ref "SV-C3") (pin "4") (pinfunction "4_4") (pintype "passive"))
    )
    (net (code "154") (name "Net-(SV-C2-Pad9)") (class "Default")
      (node (ref "SV-C2") (pin "9") (pinfunction "9_9") (pintype "passive"))
      (node (ref "SV-C3") (pin "5") (pinfunction "5_5") (pintype "passive"))
    )
    (net (code "155") (name "Net-(SV-D1-Pad1)") (class "Default")
      (node (ref "SV-D1") (pin "1") (pinfunction "1_1") (pintype "passive"))
      (node (ref "SV-D2") (pin "2") (pinfunction "2_2") (pintype "passive"))
    )
    (net (code "156") (name "Net-(SV-D1-Pad2)") (class "Default")
      (node (ref "SV-D1") (pin "2") (pinfunction "2_2") (pintype "passive"))
      (node (ref "SV-D2") (pin "4") (pinfunction "4_4") (pintype "passive"))
    )
    (net (code "157") (name "Net-(SV-D1-Pad3)") (class "Default")
      (node (ref "SV-D1") (pin "3") (pinfunction "3_3") (pintype "passive"))
      (node (ref "SV-D2") (pin "6") (pinfunction "6_6") (pintype "passive"))
    )
    (net (code "158") (name "Net-(SV-D1-Pad4)") (class "Default")
      (node (ref "SV-D1") (pin "4") (pinfunction "4_4") (pintype "passive"))
      (node (ref "SV-D2") (pin "8") (pinfunction "8_8") (pintype "passive"))
    )
    (net (code "159") (name "Net-(SV-D1-Pad5)") (class "Default")
      (node (ref "SV-D1") (pin "5") (pinfunction "5_5") (pintype "passive"))
      (node (ref "SV-D2") (pin "10") (pinfunction "10_10") (pintype "passive"))
    )
    (net (code "160") (name "Net-(SV-D1-Pad6)") (class "Default")
      (node (ref "SV-D1") (pin "6") (pinfunction "6_6") (pintype "passive"))
      (node (ref "SV-D2") (pin "12") (pinfunction "12_12") (pintype "passive"))
    )
    (net (code "161") (name "Net-(SV-D1-Pad7)") (class "Default")
      (node (ref "SV-D1") (pin "7") (pinfunction "7_7") (pintype "passive"))
      (node (ref "SV-D2") (pin "14") (pinfunction "14_14") (pintype "passive"))
    )
    (net (code "162") (name "Net-(SV-D1-Pad8)") (class "Default")
      (node (ref "SV-D1") (pin "8") (pinfunction "8_8") (pintype "passive"))
      (node (ref "SV-D2") (pin "16") (pinfunction "16_16") (pintype "passive"))
    )
    (net (code "163") (name "Net-(SV-D1-Pad9)") (class "Default")
      (node (ref "SV-D1") (pin "9") (pinfunction "9_9") (pintype "passive"))
      (node (ref "SV-D2") (pin "18") (pinfunction "18_18") (pintype "passive"))
    )
    (net (code "164") (name "Net-(SV-D1-Pad10)") (class "Default")
      (node (ref "SV-D1") (pin "10") (pinfunction "10_10") (pintype "passive"))
      (node (ref "SV-D2") (pin "20") (pinfunction "20_20") (pintype "passive"))
    )
    (net (code "165") (name "Net-(SV-D2-Pad1)") (class "Default")
      (node (ref "SV-D2") (pin "1") (pinfunction "1_1") (pintype "passive"))
      (node (ref "SVD3") (pin "1") (pinfunction "1_1") (pintype "passive"))
    )
    (net (code "166") (name "Net-(SV-D2-Pad3)") (class "Default")
      (node (ref "SV-D2") (pin "3") (pinfunction "3_3") (pintype "passive"))
      (node (ref "SVD3") (pin "2") (pinfunction "2_2") (pintype "passive"))
    )
    (net (code "167") (name "Net-(SV-D2-Pad5)") (class "Default")
      (node (ref "SV-D2") (pin "5") (pinfunction "5_5") (pintype "passive"))
      (node (ref "SVD3") (pin "3") (pinfunction "3_3") (pintype "passive"))
    )
    (net (code "168") (name "Net-(SV-D2-Pad7)") (class "Default")
      (node (ref "SV-D2") (pin "7") (pinfunction "7_7") (pintype "passive"))
      (node (ref "SVD3") (pin "4") (pinfunction "4_4") (pintype "passive"))
    )
    (net (code "169") (name "Net-(SV-D2-Pad9)") (class "Default")
      (node (ref "SV-D2") (pin "9") (pinfunction "9_9") (pintype "passive"))
      (node (ref "SVD3") (pin "5") (pinfunction "5_5") (pintype "passive"))
    )
    (net (code "170") (name "Net-(SV-D2-Pad11)") (class "Default")
      (node (ref "SV-D2") (pin "11") (pinfunction "11_11") (pintype "passive"))
      (node (ref "SVD3") (pin "6") (pinfunction "6_6") (pintype "passive"))
    )
    (net (code "171") (name "Net-(SV-D2-Pad13)") (class "Default")
      (node (ref "SV-D2") (pin "13") (pinfunction "13_13") (pintype "passive"))
      (node (ref "SVD3") (pin "7") (pinfunction "7_7") (pintype "passive"))
    )
    (net (code "172") (name "Net-(SV-D2-Pad15)") (class "Default")
      (node (ref "SV-D2") (pin "15") (pinfunction "15_15") (pintype "passive"))
      (node (ref "SVD3") (pin "8") (pinfunction "8_8") (pintype "passive"))
    )
    (net (code "173") (name "Net-(SV-D2-Pad17)") (class "Default")
      (node (ref "SV-D2") (pin "17") (pinfunction "17_17") (pintype "passive"))
      (node (ref "SVD3") (pin "9") (pinfunction "9_9") (pintype "passive"))
    )
    (net (code "174") (name "Net-(SV-D2-Pad19)") (class "Default")
      (node (ref "SV-D2") (pin "19") (pinfunction "19_19") (pintype "passive"))
      (node (ref "SVD3") (pin "10") (pinfunction "10_10") (pintype "passive"))
    )
  )
)
